# motor_hat.net
KiCad netlist of a schematic drawn in Altium Designer
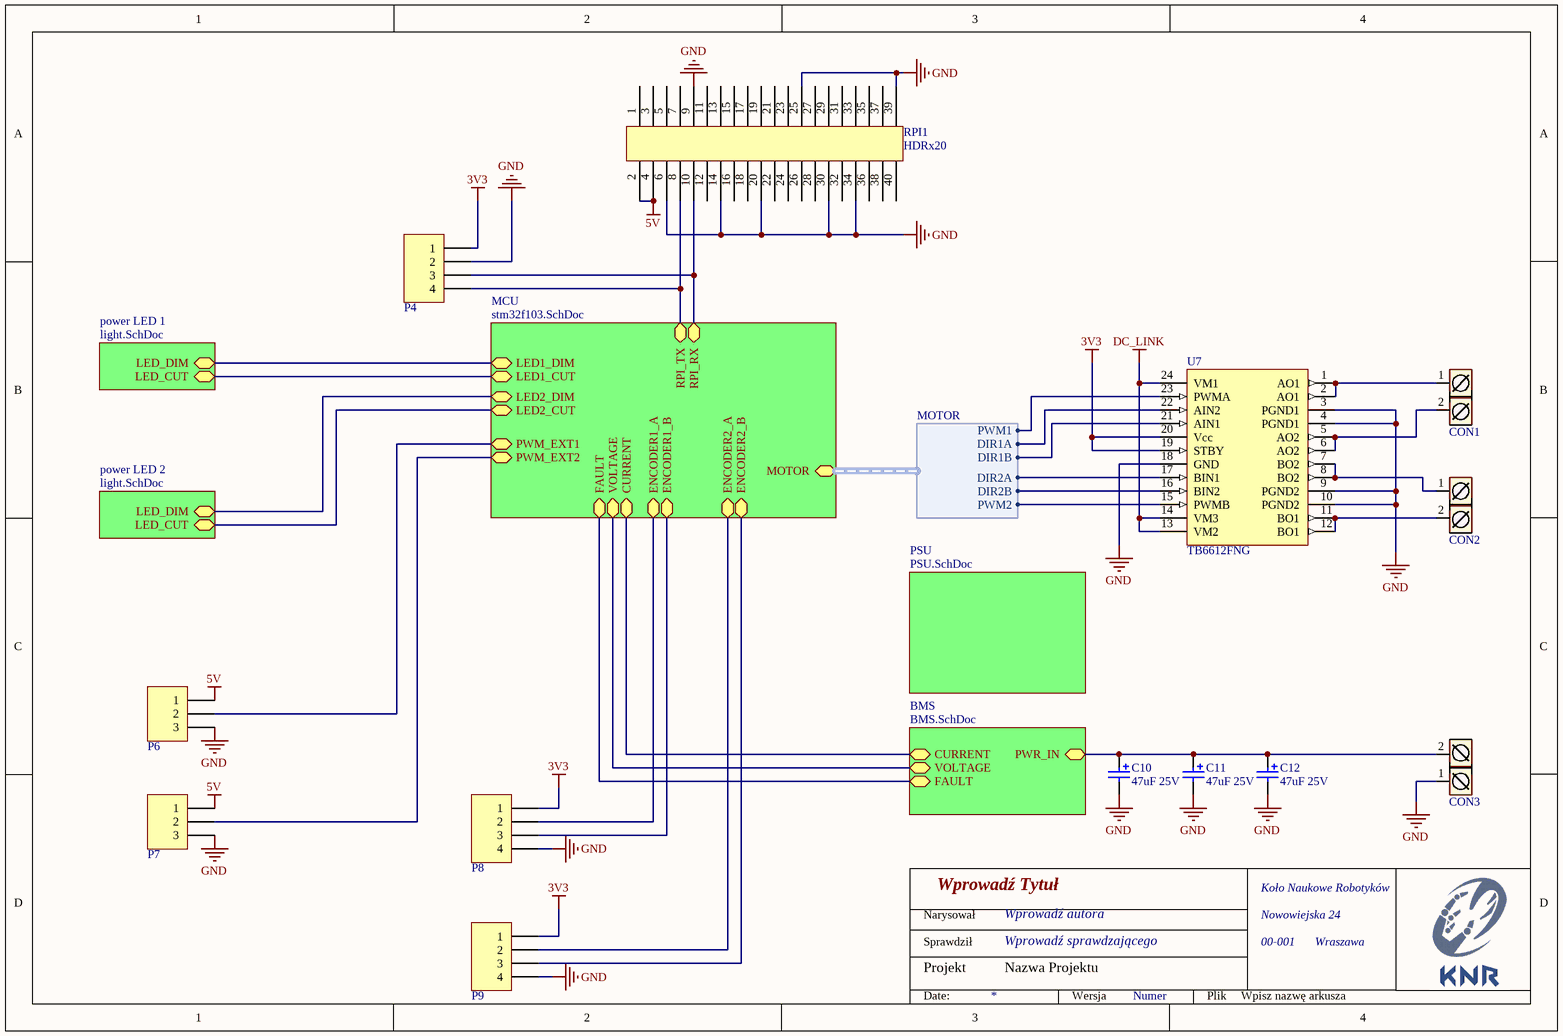
[diagram p0: motor hat.SchDoc]

(export (version "E")
  (design (tool "Eeschema 10.0.6"))
  (components
    (comp (ref "C10")
      (value "47uF 25V")
      (footprint "ELECTROLYTIC 5mm")
      (description "Electrolytic capacitor")
      (libsource (lib "Capacitors") (part "Electrolytic"))
    )
    (comp (ref "C11")
      (value "47uF 25V")
      (footprint "ELECTROLYTIC 5mm")
      (description "Electrolytic capacitor")
      (libsource (lib "Capacitors") (part "Electrolytic"))
    )
    (comp (ref "C12")
      (value "47uF 25V")
      (footprint "ELECTROLYTIC 5mm")
      (description "Electrolytic capacitor")
      (libsource (lib "Capacitors") (part "Electrolytic"))
    )
    (comp (ref "CON1")
      (value "ARK2")
      (footprint "ARK2")
      (description "Złącze śrubowe 2 piny")
      (libsource (lib "KNR_Kurs") (part "ARK2"))
    )
    (comp (ref "CON2")
      (value "ARK2")
      (footprint "ARK2")
      (description "Złącze śrubowe 2 piny")
      (libsource (lib "KNR_Kurs") (part "ARK2"))
    )
    (comp (ref "CON3")
      (value "ARK2")
      (footprint "ARK2")
      (description "Złącze śrubowe 2 piny")
      (libsource (lib "") (part "ARK2_1"))
    )
    (comp (ref "P4")
      (value "HDR1X4")
      (footprint "HDR1X4")
      (description "Header, 4-Pin")
      (fields (field (name "PUBLISHER") "Altium Limited"))
      (libsource (lib "KNR_Kurs") (part "HDR1X4"))
    )
    (comp (ref "P6")
      (value "HDR1X3")
      (footprint "HDR1X3")
      (description "Header, 3-Pin")
      (fields (field (name "PUBLISHER") "Altium Limited"))
      (libsource (lib "KNR_Kurs") (part "HDR1X3"))
    )
    (comp (ref "P7")
      (value "HDR1X3")
      (footprint "HDR1X3")
      (description "Header, 3-Pin")
      (fields (field (name "PUBLISHER") "Altium Limited"))
      (libsource (lib "KNR_Kurs") (part "HDR1X3"))
    )
    (comp (ref "P8")
      (value "HDR1X4")
      (footprint "HDR1X4")
      (description "Header, 4-Pin")
      (fields (field (name "PUBLISHER") "Altium Limited"))
      (libsource (lib "KNR_Kurs") (part "HDR1X4"))
    )
    (comp (ref "P9")
      (value "HDR1X4")
      (footprint "HDR1X4")
      (description "Header, 4-Pin")
      (fields (field (name "PUBLISHER") "Altium Limited"))
      (libsource (lib "KNR_Kurs") (part "HDR1X4"))
    )
    (comp (ref "RPI1") (value "HDRx20") (footprint "HDR2x20") (libsource (lib "Robo_leon") (part "HDRx20")))
    (comp (ref "U7")
      (value "TB6612FNG")
      (footprint "SSOP24-P-300")
      (description "Driver IC for Dual DC motor")
      (libsource (lib "KNR_Kurs") (part "TB6612FNG"))
    )
  )
  (nets
    (net (code "3") (name "/DIR1A") (class "Default")
      (node (ref "U7") (pin "22") (pinfunction "AIN2_22") (pintype "input"))
    )
    (net (code "4") (name "/DIR1B") (class "Default")
      (node (ref "U7") (pin "21") (pinfunction "AIN1_21") (pintype "input"))
    )
    (net (code "5") (name "/DIR2A") (class "Default")
      (node (ref "U7") (pin "17") (pinfunction "BIN1_17") (pintype "input"))
    )
    (net (code "6") (name "/DIR2B") (class "Default")
      (node (ref "U7") (pin "16") (pinfunction "BIN2_16") (pintype "input"))
    )
    (net (code "7") (name "/ENCODER1_A") (class "Default")
      (node (ref "P8") (pin "2") (pinfunction "2_2") (pintype "passive"))
    )
    (net (code "8") (name "/ENCODER1_B") (class "Default")
      (node (ref "P8") (pin "3") (pinfunction "3_3") (pintype "passive"))
    )
    (net (code "9") (name "/ENCODER2_A") (class "Default")
      (node (ref "P9") (pin "2") (pinfunction "2_2") (pintype "passive"))
    )
    (net (code "10") (name "/ENCODER2_B") (class "Default")
      (node (ref "P9") (pin "3") (pinfunction "3_3") (pintype "passive"))
    )
    (net (code "16") (name "/PWM1") (class "Default")
      (node (ref "U7") (pin "23") (pinfunction "PWMA_23") (pintype "input"))
    )
    (net (code "17") (name "/PWM2") (class "Default")
      (node (ref "U7") (pin "15") (pinfunction "PWMB_15") (pintype "input"))
    )
    (net (code "18") (name "/PWM_EXT1") (class "Default")
      (node (ref "P6") (pin "2") (pinfunction "2_2") (pintype "passive"))
    )
    (net (code "19") (name "/PWM_EXT2") (class "Default")
      (node (ref "P7") (pin "2") (pinfunction "2_2") (pintype "passive"))
    )
    (net (code "20") (name "/PWR_IN") (class "Default")
      (node (ref "C10") (pin "1") (pinfunction "1_1") (pintype "passive"))
      (node (ref "C11") (pin "1") (pinfunction "1_1") (pintype "passive"))
      (node (ref "C12") (pin "1") (pinfunction "1_1") (pintype "passive"))
      (node (ref "CON3") (pin "2") (pinfunction "2_2") (pintype "passive"))
    )
    (net (code "21") (name "/RPI_RX") (class "Default")
      (node (ref "P4") (pin "3") (pinfunction "3_3") (pintype "passive"))
      (node (ref "RPI1") (pin "10") (pinfunction "10_10") (pintype "passive"))
    )
    (net (code "22") (name "/RPI_TX") (class "Default")
      (node (ref "P4") (pin "4") (pinfunction "4_4") (pintype "passive"))
      (node (ref "RPI1") (pin "8") (pinfunction "8_8") (pintype "passive"))
    )
    (net (code "25") (name "3V3") (class "Default")
      (node (ref "P4") (pin "1") (pinfunction "1_1") (pintype "passive"))
      (node (ref "P8") (pin "1") (pinfunction "1_1") (pintype "passive"))
      (node (ref "P9") (pin "1") (pinfunction "1_1") (pintype "passive"))
      (node (ref "U7") (pin "19") (pinfunction "STBY_19") (pintype "input"))
      (node (ref "U7") (pin "20") (pinfunction "Vcc_20") (pintype "passive"))
    )
    (net (code "26") (name "5V") (class "Default")
      (node (ref "P6") (pin "1") (pinfunction "1_1") (pintype "passive"))
      (node (ref "P7") (pin "1") (pinfunction "1_1") (pintype "passive"))
      (node (ref "RPI1") (pin "2") (pinfunction "2_2") (pintype "passive"))
      (node (ref "RPI1") (pin "4") (pinfunction "4_4") (pintype "passive"))
    )
    (net (code "27") (name "DC_LINK") (class "Default")
      (node (ref "U7") (pin "13") (pinfunction "VM2_13") (pintype "power_in"))
      (node (ref "U7") (pin "14") (pinfunction "VM3_14") (pintype "power_in"))
      (node (ref "U7") (pin "24") (pinfunction "VM1_24") (pintype "power_in"))
    )
    (net (code "28") (name "GND") (class "Default")
      (node (ref "C10") (pin "2") (pinfunction "2_2") (pintype "passive"))
      (node (ref "C11") (pin "2") (pinfunction "2_2") (pintype "passive"))
      (node (ref "C12") (pin "2") (pinfunction "2_2") (pintype "passive"))
      (node (ref "CON3") (pin "1") (pinfunction "1_1") (pintype "passive"))
      (node (ref "P4") (pin "2") (pinfunction "2_2") (pintype "passive"))
      (node (ref "P6") (pin "3") (pinfunction "3_3") (pintype "passive"))
      (node (ref "P7") (pin "3") (pinfunction "3_3") (pintype "passive"))
      (node (ref "P8") (pin "4") (pinfunction "4_4") (pintype "passive"))
      (node (ref "P9") (pin "4") (pinfunction "4_4") (pintype "passive"))
      (node (ref "RPI1") (pin "14") (pinfunction "14_14") (pintype "passive"))
      (node (ref "RPI1") (pin "20") (pinfunction "20_20") (pintype "passive"))
      (node (ref "RPI1") (pin "25") (pinfunction "25_25") (pintype "passive"))
      (node (ref "RPI1") (pin "30") (pinfunction "30_30") (pintype "passive"))
      (node (ref "RPI1") (pin "34") (pinfunction "34_34") (pintype "passive"))
      (node (ref "RPI1") (pin "39") (pinfunction "39_39") (pintype "passive"))
      (node (ref "RPI1") (pin "6") (pinfunction "6_6") (pintype "passive"))
      (node (ref "RPI1") (pin "9") (pinfunction "9_9") (pintype "passive"))
      (node (ref "U7") (pin "10") (pinfunction "PGND2_10") (pintype "passive"))
      (node (ref "U7") (pin "18") (pinfunction "GND_18") (pintype "passive"))
      (node (ref "U7") (pin "3") (pinfunction "PGND1_3") (pintype "passive"))
      (node (ref "U7") (pin "4") (pinfunction "PGND1_4") (pintype "passive"))
      (node (ref "U7") (pin "9") (pinfunction "PGND2_9") (pintype "passive"))
    )
    (net (code "29") (name "Net-(CON1-Pad1)") (class "Default")
      (node (ref "CON1") (pin "1") (pinfunction "1_1") (pintype "passive"))
      (node (ref "U7") (pin "1") (pinfunction "AO1_1") (pintype "output"))
      (node (ref "U7") (pin "2") (pinfunction "AO1_2") (pintype "output"))
    )
    (net (code "30") (name "Net-(CON1-Pad2)") (class "Default")
      (node (ref "CON1") (pin "2") (pinfunction "2_2") (pintype "passive"))
      (node (ref "U7") (pin "5") (pinfunction "AO2_5") (pintype "output"))
      (node (ref "U7") (pin "6") (pinfunction "AO2_6") (pintype "output"))
    )
    (net (code "31") (name "Net-(CON2-Pad1)") (class "Default")
      (node (ref "CON2") (pin "1") (pinfunction "1_1") (pintype "passive"))
      (node (ref "U7") (pin "7") (pinfunction "BO2_7") (pintype "output"))
      (node (ref "U7") (pin "8") (pinfunction "BO2_8") (pintype "output"))
    )
    (net (code "32") (name "Net-(CON2-Pad2)") (class "Default")
      (node (ref "CON2") (pin "2") (pinfunction "2_2") (pintype "passive"))
      (node (ref "U7") (pin "11") (pinfunction "BO1_11") (pintype "output"))
      (node (ref "U7") (pin "12") (pinfunction "BO1_12") (pintype "output"))
    )
    (net (code "33") (name "unconnected-(RPI1-Pad1)") (class "Default")
      (node (ref "RPI1") (pin "1") (pinfunction "1_1") (pintype "passive"))
    )
    (net (code "34") (name "unconnected-(RPI1-Pad3)") (class "Default")
      (node (ref "RPI1") (pin "3") (pinfunction "3_3") (pintype "passive"))
    )
    (net (code "35") (name "unconnected-(RPI1-Pad5)") (class "Default")
      (node (ref "RPI1") (pin "5") (pinfunction "5_5") (pintype "passive"))
    )
    (net (code "36") (name "unconnected-(RPI1-Pad7)") (class "Default")
      (node (ref "RPI1") (pin "7") (pinfunction "7_7") (pintype "passive"))
    )
    (net (code "37") (name "unconnected-(RPI1-Pad11)") (class "Default")
      (node (ref "RPI1") (pin "11") (pinfunction "11_11") (pintype "passive"))
    )
    (net (code "38") (name "unconnected-(RPI1-Pad12)") (class "Default")
      (node (ref "RPI1") (pin "12") (pinfunction "12_12") (pintype "passive"))
    )
    (net (code "39") (name "unconnected-(RPI1-Pad13)") (class "Default")
      (node (ref "RPI1") (pin "13") (pinfunction "13_13") (pintype "passive"))
    )
    (net (code "40") (name "unconnected-(RPI1-Pad15)") (class "Default")
      (node (ref "RPI1") (pin "15") (pinfunction "15_15") (pintype "passive"))
    )
    (net (code "41") (name "unconnected-(RPI1-Pad16)") (class "Default")
      (node (ref "RPI1") (pin "16") (pinfunction "16_16") (pintype "passive"))
    )
    (net (code "42") (name "unconnected-(RPI1-Pad17)") (class "Default")
      (node (ref "RPI1") (pin "17") (pinfunction "17_17") (pintype "passive"))
    )
    (net (code "43") (name "unconnected-(RPI1-Pad18)") (class "Default")
      (node (ref "RPI1") (pin "18") (pinfunction "18_18") (pintype "passive"))
    )
    (net (code "44") (name "unconnected-(RPI1-Pad19)") (class "Default")
      (node (ref "RPI1") (pin "19") (pinfunction "19_19") (pintype "passive"))
    )
    (net (code "45") (name "unconnected-(RPI1-Pad21)") (class "Default")
      (node (ref "RPI1") (pin "21") (pinfunction "21_21") (pintype "passive"))
    )
    (net (code "46") (name "unconnected-(RPI1-Pad22)") (class "Default")
      (node (ref "RPI1") (pin "22") (pinfunction "22_22") (pintype "passive"))
    )
    (net (code "47") (name "unconnected-(RPI1-Pad23)") (class "Default")
      (node (ref "RPI1") (pin "23") (pinfunction "23_23") (pintype "passive"))
    )
    (net (code "48") (name "unconnected-(RPI1-Pad24)") (class "Default")
      (node (ref "RPI1") (pin "24") (pinfunction "24_24") (pintype "passive"))
    )
    (net (code "49") (name "unconnected-(RPI1-Pad26)") (class "Default")
      (node (ref "RPI1") (pin "26") (pinfunction "26_26") (pintype "passive"))
    )
    (net (code "50") (name "unconnected-(RPI1-Pad27)") (class "Default")
      (node (ref "RPI1") (pin "27") (pinfunction "27_27") (pintype "passive"))
    )
    (net (code "51") (name "unconnected-(RPI1-Pad28)") (class "Default")
      (node (ref "RPI1") (pin "28") (pinfunction "28_28") (pintype "passive"))
    )
    (net (code "52") (name "unconnected-(RPI1-Pad29)") (class "Default")
      (node (ref "RPI1") (pin "29") (pinfunction "29_29") (pintype "passive"))
    )
    (net (code "53") (name "unconnected-(RPI1-Pad31)") (class "Default")
      (node (ref "RPI1") (pin "31") (pinfunction "31_31") (pintype "passive"))
    )
    (net (code "54") (name "unconnected-(RPI1-Pad32)") (class "Default")
      (node (ref "RPI1") (pin "32") (pinfunction "32_32") (pintype "passive"))
    )
    (net (code "55") (name "unconnected-(RPI1-Pad33)") (class "Default")
      (node (ref "RPI1") (pin "33") (pinfunction "33_33") (pintype "passive"))
    )
    (net (code "56") (name "unconnected-(RPI1-Pad35)") (class "Default")
      (node (ref "RPI1") (pin "35") (pinfunction "35_35") (pintype "passive"))
    )
    (net (code "57") (name "unconnected-(RPI1-Pad36)") (class "Default")
      (node (ref "RPI1") (pin "36") (pinfunction "36_36") (pintype "passive"))
    )
    (net (code "58") (name "unconnected-(RPI1-Pad37)") (class "Default")
      (node (ref "RPI1") (pin "37") (pinfunction "37_37") (pintype "passive"))
    )
    (net (code "59") (name "unconnected-(RPI1-Pad38)") (class "Default")
      (node (ref "RPI1") (pin "38") (pinfunction "38_38") (pintype "passive"))
    )
    (net (code "60") (name "unconnected-(RPI1-Pad40)") (class "Default")
      (node (ref "RPI1") (pin "40") (pinfunction "40_40") (pintype "passive"))
    )
  )
)
